# solar_charger.net
KiCad netlist of a schematic drawn in Altium Designer
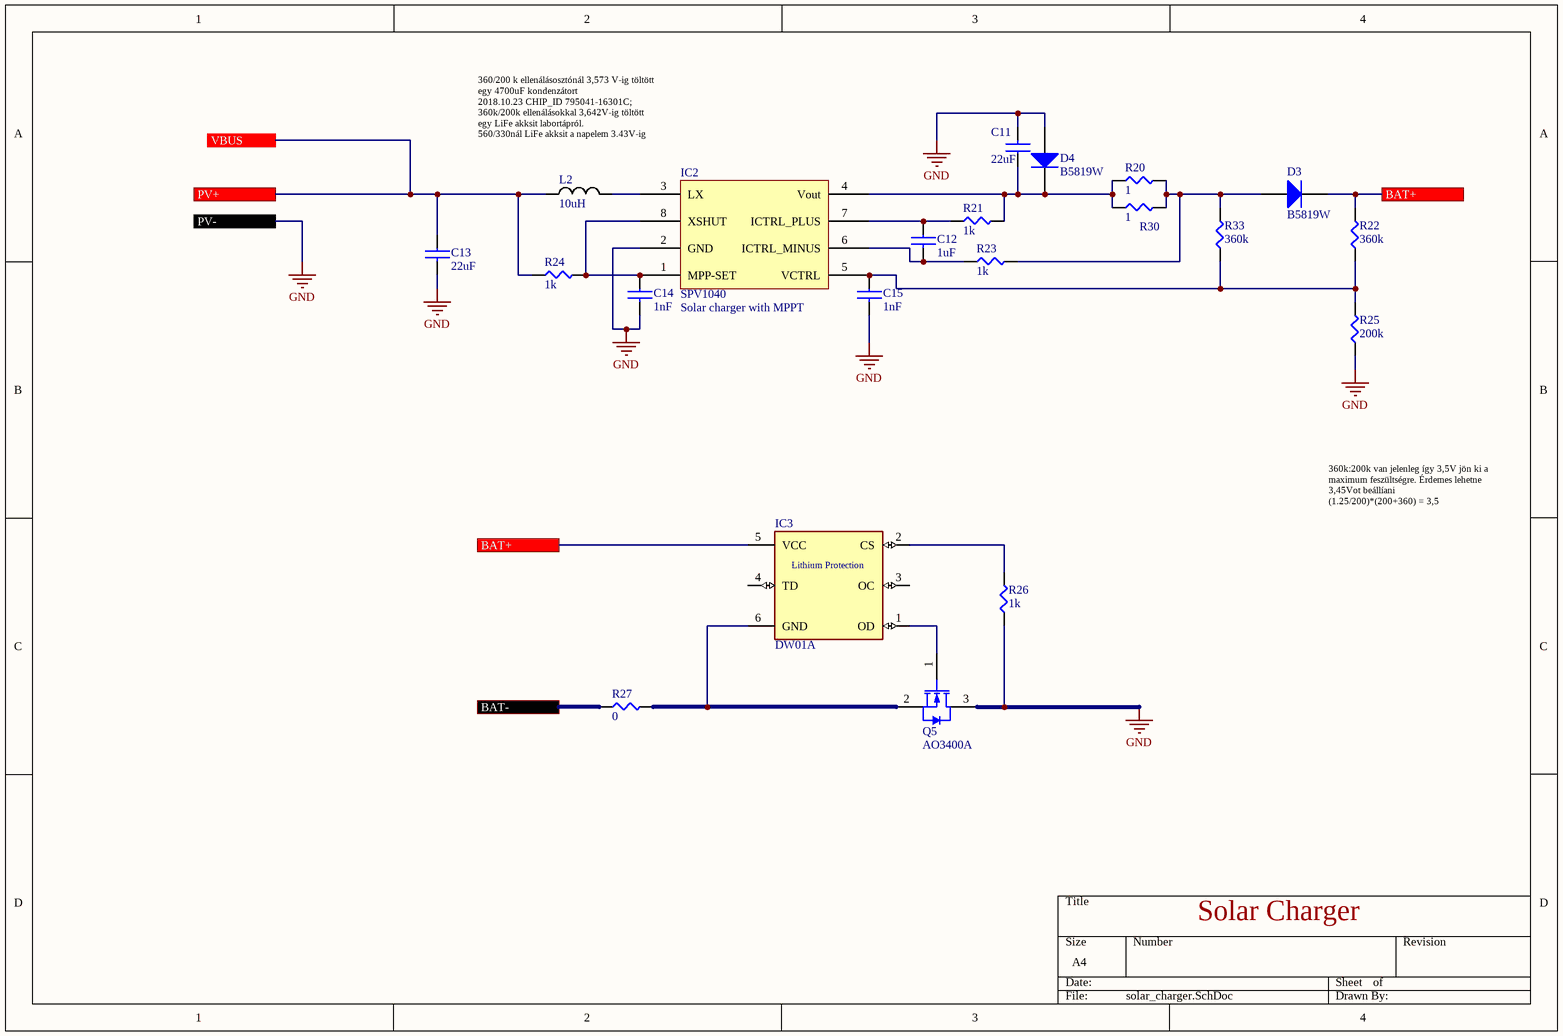
[diagram p0: solar_charger.SchDoc]

(export (version "E")
  (design (tool "Eeschema 10.0.6"))
  (components
    (comp (ref "C11")
      (value "22uF")
      (footprint "CAPC200X125X110L50N")
      (fields (field (name "LCSC PART #") "C59461"))
      (libsource (lib "WateringSystem_lib") (part "Capacitor"))
    )
    (comp (ref "C12")
      (value "1uF")
      (footprint "CAPC200X125X110L50N")
      (fields (field (name "LCSC PART #") "C15849"))
      (libsource (lib "WateringSystem_lib") (part "Capacitor"))
    )
    (comp (ref "C13")
      (value "22uF")
      (footprint "CAPC200X125X110L50N")
      (fields (field (name "LCSC PART #") "C59461"))
      (libsource (lib "WateringSystem_lib") (part "Capacitor"))
    )
    (comp (ref "C14")
      (value "1nF")
      (footprint "CAPC160X80X90L35N")
      (fields (field (name "LCSC PART #") "C1588"))
      (libsource (lib "WateringSystem_lib") (part "Capacitor"))
    )
    (comp (ref "C15")
      (value "1nF")
      (footprint "CAPC160X80X90L35N")
      (fields (field (name "LCSC PART #") "C1588"))
      (libsource (lib "WateringSystem_lib") (part "Capacitor"))
    )
    (comp (ref "D3")
      (value "B5819W")
      (footprint "SODFL350X110-2N")
      (fields (field (name "LCSC PART #") "C8598"))
      (libsource (lib "WateringSystem_lib") (part "Diode"))
    )
    (comp (ref "D4")
      (value "B5819W")
      (footprint "SODFL350X110-2N")
      (fields (field (name "LCSC PART #") "C8598"))
      (libsource (lib "WateringSystem_lib") (part "Diode"))
    )
    (comp (ref "IC2")
      (value "SPV1040")
      (footprint "SPV1040")
      (fields (field (name "LCSC PART #") "C221500"))
      (libsource (lib "WateringSystem_lib") (part "SPV1040"))
    )
    (comp (ref "IC3")
      (value "DW01A")
      (footprint "CFP6P95_290X280X145L45X40N")
      (description "Pushbutton Switch SPST-NC Standard Panel Mount, Front")
      (fields (field (name "MF") "Fortune Semiconductor") (field (name "LCSC PART #") "C61503"))
      (libsource (lib "WateringSystem_lib") (part "DW01A"))
    )
    (comp (ref "L2")
      (value "10uH")
      (footprint "INDM730X660X300L160X290N")
      (description "INDUCTOR")
      (fields (field (name "LCSC PART #") "C132141"))
      (libsource (lib "WateringSystem_lib") (part "INDUCTOR"))
    )
    (comp (ref "Q5")
      (value "AO3400A")
      (footprint "SOT23-3P95_240X114L20X40N")
      (description "N-FET")
      (fields (field (name "LCSC PART #") "C20917"))
      (libsource (lib "WateringSystem_lib") (part "N-FET"))
    )
    (comp (ref "R20")
      (value "1")
      (footprint "RESC160X80X90L30N")
      (fields (field (name "LCSC PART #") "C22936"))
      (libsource (lib "WateringSystem_lib") (part "Resistor"))
    )
    (comp (ref "R21")
      (value "1k")
      (footprint "RESC200X125X70L40N")
      (fields (field (name "LCSC PART #") "C17513"))
      (libsource (lib "WateringSystem_lib") (part "Resistor"))
    )
    (comp (ref "R22")
      (value "360k")
      (footprint "RESC160X80X90L30N")
      (fields (field (name "LCSC PART #") "C23146"))
      (libsource (lib "WateringSystem_lib") (part "Resistor"))
    )
    (comp (ref "R23")
      (value "1k")
      (footprint "RESC200X125X70L40N")
      (fields (field (name "LCSC PART #") "C17513"))
      (libsource (lib "WateringSystem_lib") (part "Resistor"))
    )
    (comp (ref "R24")
      (value "1k")
      (footprint "RESC200X125X70L40N")
      (fields (field (name "LCSC PART #") "C17513"))
      (libsource (lib "WateringSystem_lib") (part "Resistor"))
    )
    (comp (ref "R25")
      (value "200k")
      (footprint "RESC200X125X70L40N")
      (fields (field (name "LCSC PART #") "C17539"))
      (libsource (lib "WateringSystem_lib") (part "Resistor"))
    )
    (comp (ref "R26")
      (value "1k")
      (footprint "RESC200X125X70L40N")
      (fields (field (name "LCSC PART #") "C17513"))
      (libsource (lib "WateringSystem_lib") (part "Resistor"))
    )
    (comp (ref "R27")
      (value "0")
      (footprint "RESC200X125X70L40N")
      (description "This is a fuse!!!")
      (fields (field (name "LCSC PART #") "C17477"))
      (libsource (lib "WateringSystem_lib") (part "Resistor"))
    )
    (comp (ref "R30")
      (value "1")
      (footprint "RESC160X80X90L30N")
      (fields (field (name "LCSC PART #") "C22936"))
      (libsource (lib "WateringSystem_lib") (part "Resistor"))
    )
    (comp (ref "R33")
      (value "360k")
      (footprint "RESC160X80X90L30N")
      (fields (field (name "LCSC PART #") "not polluted"))
      (libsource (lib "WateringSystem_lib") (part "Resistor"))
    )
  )
  (nets
    (net (code "1") (name "/BAT+") (class "Default")
      (node (ref "D3") (pin "C") (pinfunction "C_C") (pintype "passive"))
      (node (ref "IC3") (pin "5") (pinfunction "VCC_5") (pintype "power_in"))
      (node (ref "R22") (pin "2") (pinfunction "2_2") (pintype "passive"))
    )
    (net (code "2") (name "/BAT-") (class "Default")
      (node (ref "R27") (pin "1") (pinfunction "1_1") (pintype "passive"))
    )
    (net (code "3") (name "/PV+") (class "Default")
      (node (ref "C13") (pin "1") (pinfunction "1_1") (pintype "passive"))
      (node (ref "L2") (pin "1") (pinfunction "1_1") (pintype "passive"))
      (node (ref "R24") (pin "1") (pinfunction "1_1") (pintype "passive"))
    )
    (net (code "4") (name "GND") (class "Default")
      (node (ref "C11") (pin "2") (pinfunction "2_2") (pintype "passive"))
      (node (ref "C13") (pin "2") (pinfunction "2_2") (pintype "passive"))
      (node (ref "C14") (pin "2") (pinfunction "2_2") (pintype "passive"))
      (node (ref "C15") (pin "2") (pinfunction "2_2") (pintype "passive"))
      (node (ref "D4") (pin "A") (pinfunction "A_A") (pintype "passive"))
      (node (ref "IC2") (pin "2") (pinfunction "GND_2") (pintype "passive"))
      (node (ref "Q5") (pin "3") (pinfunction "DRAIN_3") (pintype "passive"))
      (node (ref "R25") (pin "1") (pinfunction "1_1") (pintype "passive"))
      (node (ref "R26") (pin "1") (pinfunction "1_1") (pintype "passive"))
    )
    (net (code "5") (name "Net-(D3-PadA)") (class "Default")
      (node (ref "D3") (pin "A") (pinfunction "A_A") (pintype "passive"))
      (node (ref "R20") (pin "2") (pinfunction "2_2") (pintype "passive"))
      (node (ref "R23") (pin "2") (pinfunction "2_2") (pintype "passive"))
      (node (ref "R30") (pin "2") (pinfunction "2_2") (pintype "passive"))
      (node (ref "R33") (pin "2") (pinfunction "2_2") (pintype "passive"))
    )
    (net (code "6") (name "Net-(IC2-ICTRL_MINUS)") (class "Default")
      (node (ref "C12") (pin "2") (pinfunction "2_2") (pintype "passive"))
      (node (ref "IC2") (pin "6") (pinfunction "ICTRL_MINUS_6") (pintype "passive"))
      (node (ref "R23") (pin "1") (pinfunction "1_1") (pintype "passive"))
    )
    (net (code "7") (name "Net-(IC2-ICTRL_PLUS)") (class "Default")
      (node (ref "C12") (pin "1") (pinfunction "1_1") (pintype "passive"))
      (node (ref "IC2") (pin "7") (pinfunction "ICTRL_PLUS_7") (pintype "passive"))
      (node (ref "R21") (pin "1") (pinfunction "1_1") (pintype "passive"))
    )
    (net (code "8") (name "Net-(IC2-LX)") (class "Default")
      (node (ref "IC2") (pin "3") (pinfunction "LX_3") (pintype "passive"))
      (node (ref "L2") (pin "2") (pinfunction "2_2") (pintype "passive"))
    )
    (net (code "9") (name "Net-(IC2-MPP-SET)") (class "Default")
      (node (ref "C14") (pin "1") (pinfunction "1_1") (pintype "passive"))
      (node (ref "IC2") (pin "1") (pinfunction "MPP-SET_1") (pintype "passive"))
      (node (ref "IC2") (pin "8") (pinfunction "XSHUT_8") (pintype "passive"))
      (node (ref "R24") (pin "2") (pinfunction "2_2") (pintype "passive"))
    )
    (net (code "10") (name "Net-(IC2-VCTRL)") (class "Default")
      (node (ref "C15") (pin "1") (pinfunction "1_1") (pintype "passive"))
      (node (ref "IC2") (pin "5") (pinfunction "VCTRL_5") (pintype "passive"))
      (node (ref "R22") (pin "1") (pinfunction "1_1") (pintype "passive"))
      (node (ref "R25") (pin "2") (pinfunction "2_2") (pintype "passive"))
      (node (ref "R33") (pin "1") (pinfunction "1_1") (pintype "passive"))
    )
    (net (code "11") (name "Net-(IC2-Vout)") (class "Default")
      (node (ref "C11") (pin "1") (pinfunction "1_1") (pintype "passive"))
      (node (ref "D4") (pin "C") (pinfunction "C_C") (pintype "passive"))
      (node (ref "IC2") (pin "4") (pinfunction "Vout_4") (pintype "passive"))
      (node (ref "R20") (pin "1") (pinfunction "1_1") (pintype "passive"))
      (node (ref "R21") (pin "2") (pinfunction "2_2") (pintype "passive"))
      (node (ref "R30") (pin "1") (pinfunction "1_1") (pintype "passive"))
    )
    (net (code "12") (name "Net-(IC3-CS)") (class "Default")
      (node (ref "IC3") (pin "2") (pinfunction "CS_2") (pintype "bidirectional"))
      (node (ref "R26") (pin "2") (pinfunction "2_2") (pintype "passive"))
    )
    (net (code "13") (name "Net-(IC3-GND)") (class "Default")
      (node (ref "IC3") (pin "6") (pinfunction "GND_6") (pintype "power_in"))
      (node (ref "Q5") (pin "2") (pinfunction "SOURCE_2") (pintype "passive"))
      (node (ref "R27") (pin "2") (pinfunction "2_2") (pintype "passive"))
    )
    (net (code "14") (name "Net-(IC3-OD)") (class "Default")
      (node (ref "IC3") (pin "1") (pinfunction "OD_1") (pintype "bidirectional"))
      (node (ref "Q5") (pin "1") (pinfunction "GATE_1") (pintype "passive"))
    )
    (net (code "15") (name "unconnected-(IC3-OC-Pad3)") (class "Default")
      (node (ref "IC3") (pin "3") (pinfunction "OC_3") (pintype "bidirectional"))
    )
    (net (code "16") (name "unconnected-(IC3-TD-Pad4)") (class "Default")
      (node (ref "IC3") (pin "4") (pinfunction "TD_4") (pintype "bidirectional"))
    )
  )
)
